# pci_fonte.net
KiCad netlist of a schematic drawn in EAGLE
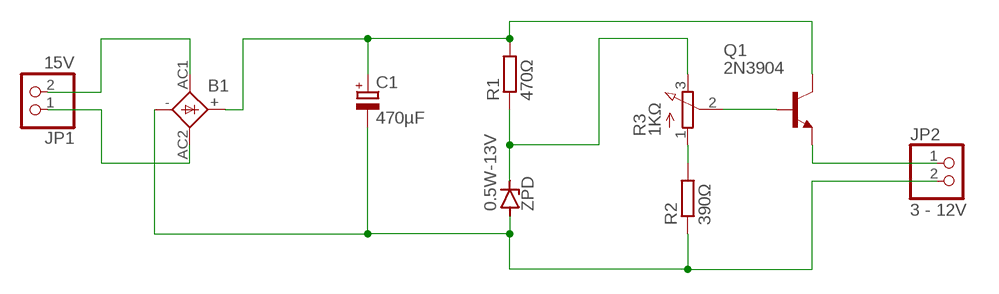
[diagram p0: schematic, sheet 1]

(export (version "E")
  (design (tool "Eeschema 10.0.6"))
  (components
    (comp (ref "0.5W-13V")
      (value "ZPD")
      (footprint "eagle-import:DO35Z10")
      (libsource (lib "eagle-import") (part "ZPD"))
    )
    (comp (ref "B1")
      (value "1KAB")
      (footprint "eagle-import:1KAB")
      (libsource (lib "eagle-import") (part "1KAB"))
    )
    (comp (ref "C1")
      (value "470µF")
      (footprint "eagle-import:E3,5-10")
      (libsource (lib "eagle-import") (part "CPOL-EUE3.5-10"))
    )
    (comp (ref "JP1")
      (value "15V")
      (footprint "eagle-import:1X02")
      (libsource (lib "eagle-import") (part "PINHD-1X2"))
    )
    (comp (ref "JP2")
      (value "3 - 12V")
      (footprint "eagle-import:1X02")
      (libsource (lib "eagle-import") (part "PINHD-1X2"))
    )
    (comp (ref "Q1")
      (value "2N3904")
      (footprint "eagle-import:TO92")
      (libsource (lib "eagle-import") (part "2N3904"))
    )
    (comp (ref "R1")
      (value "470Ω")
      (footprint "eagle-import:0204_7")
      (libsource (lib "eagle-import") (part "R-EU_0204/7"))
    )
    (comp (ref "R2")
      (value "390Ω")
      (footprint "eagle-import:0204_7")
      (libsource (lib "eagle-import") (part "R-EU_0204/7"))
    )
    (comp (ref "R3")
      (value "1KΩ")
      (footprint "eagle-import:3RP_1610N")
      (libsource (lib "eagle-import") (part "3RP/1610N"))
    )
  )
  (nets
    (net (code "1") (name "Net-(0.5W-13V-PadA)") (class "Default")
      (node (ref "0.5W-13V") (pin "A") (pinfunction "A_A") (pintype "passive"))
      (node (ref "B1") (pin "-") (pinfunction "-_-") (pintype "passive"))
      (node (ref "C1") (pin "-") (pinfunction "-_-") (pintype "passive"))
      (node (ref "JP2") (pin "2") (pinfunction "2_2") (pintype "passive"))
      (node (ref "R2") (pin "1") (pinfunction "1_1") (pintype "passive"))
    )
    (net (code "2") (name "Net-(B1-PadAC1)") (class "Default")
      (node (ref "B1") (pin "AC1") (pinfunction "AC1_AC1") (pintype "passive"))
      (node (ref "JP1") (pin "2") (pinfunction "2_2") (pintype "passive"))
    )
    (net (code "3") (name "Net-(B1-PadAC2)") (class "Default")
      (node (ref "B1") (pin "AC2") (pinfunction "AC2_AC2") (pintype "passive"))
      (node (ref "JP1") (pin "1") (pinfunction "1_1") (pintype "passive"))
    )
    (net (code "4") (name "Net-(Q1-B)") (class "Default")
      (node (ref "Q1") (pin "2") (pinfunction "B_2") (pintype "passive"))
      (node (ref "R3") (pin "2") (pinfunction "S_2") (pintype "passive"))
    )
    (net (code "5") (name "Net-(Q1-C)") (class "Default")
      (node (ref "B1") (pin "+") (pinfunction "+_+") (pintype "passive"))
      (node (ref "C1") (pin "+") (pinfunction "+_+") (pintype "passive"))
      (node (ref "Q1") (pin "1") (pinfunction "C_1") (pintype "passive"))
      (node (ref "R1") (pin "2") (pinfunction "2_2") (pintype "passive"))
    )
    (net (code "6") (name "Net-(Q1-E)") (class "Default")
      (node (ref "JP2") (pin "1") (pinfunction "1_1") (pintype "passive"))
      (node (ref "Q1") (pin "3") (pinfunction "E_3") (pintype "passive"))
    )
    (net (code "7") (name "Net-(R3-A)") (class "Default")
      (node (ref "R2") (pin "2") (pinfunction "2_2") (pintype "passive"))
      (node (ref "R3") (pin "1") (pinfunction "A_1") (pintype "passive"))
    )
    (net (code "8") (name "Net-(R3-E)") (class "Default")
      (node (ref "0.5W-13V") (pin "C") (pinfunction "C_C") (pintype "passive"))
      (node (ref "R1") (pin "1") (pinfunction "1_1") (pintype "passive"))
      (node (ref "R3") (pin "3") (pinfunction "E_3") (pintype "passive"))
    )
  )
)
